# led-er.net
KiCad netlist of a schematic drawn in EAGLE
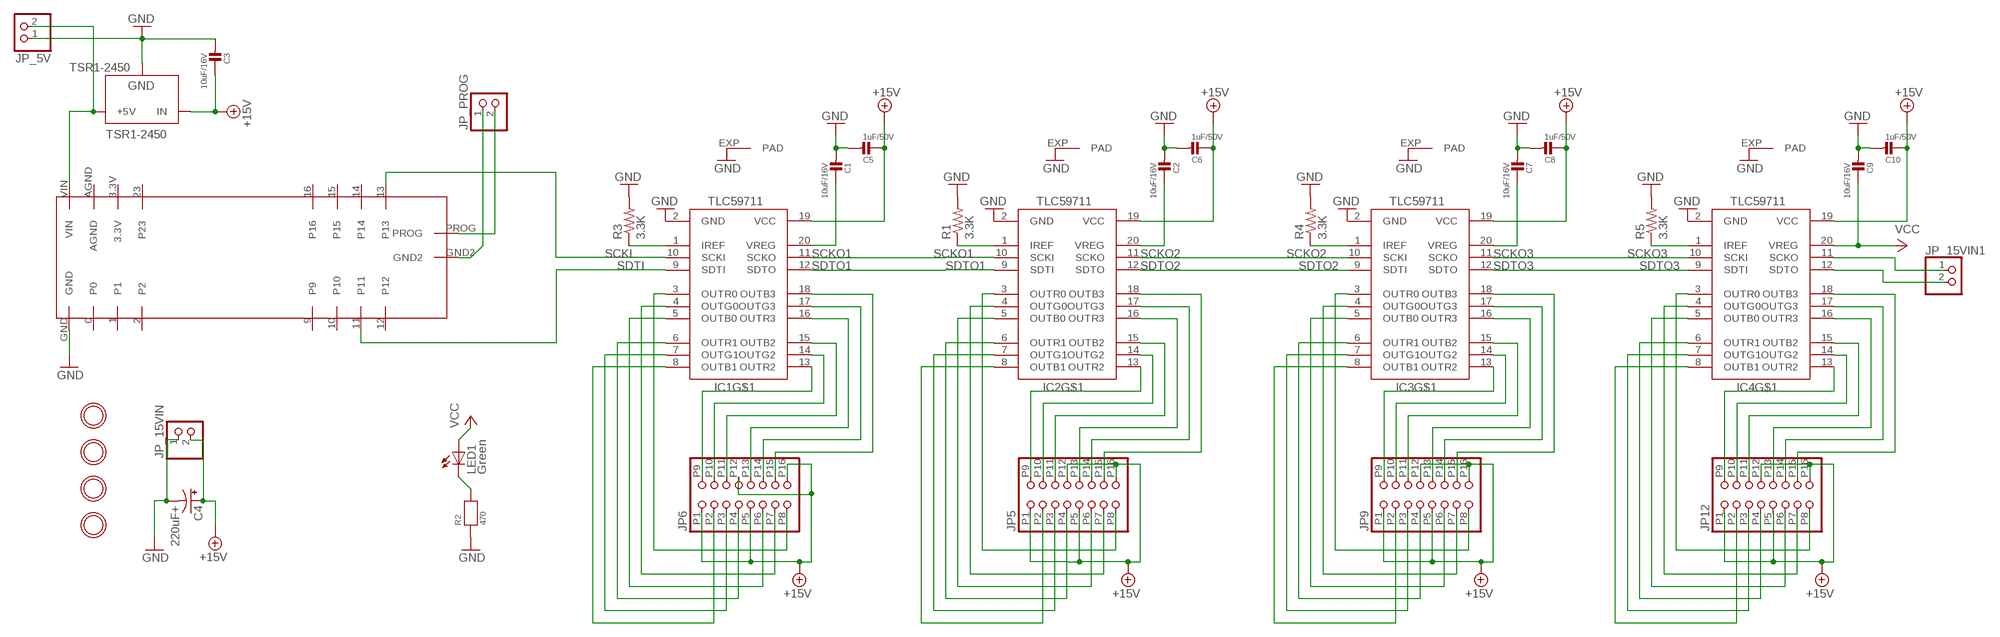
[diagram p0: schematic, sheet 1]

(export (version "E")
  (design (tool "Eeschema 10.0.6"))
  (components
    (comp (ref "C1")
      (value "10uF/16V")
      (footprint "eagle-import:0805")
      (libsource (lib "eagle-import") (part "CAP_CERAMIC0805"))
    )
    (comp (ref "C2")
      (value "10uF/16V")
      (footprint "eagle-import:0805")
      (libsource (lib "eagle-import") (part "CAP_CERAMIC0805"))
    )
    (comp (ref "C3")
      (value "10uF/16V")
      (footprint "eagle-import:0805")
      (libsource (lib "eagle-import") (part "CAP_CERAMIC0805"))
    )
    (comp (ref "C4")
      (value "220uF+")
      (footprint "eagle-import:E5-8,5")
      (libsource (lib "eagle-import") (part "CPOL-USE5-8.5"))
    )
    (comp (ref "C5")
      (value "1uF/50V")
      (footprint "eagle-import:0805")
      (libsource (lib "eagle-import") (part "CAP_CERAMIC0805"))
    )
    (comp (ref "C6")
      (value "1uF/50V")
      (footprint "eagle-import:0805")
      (libsource (lib "eagle-import") (part "CAP_CERAMIC0805"))
    )
    (comp (ref "C7")
      (value "10uF/16V")
      (footprint "eagle-import:0805")
      (libsource (lib "eagle-import") (part "CAP_CERAMIC0805"))
    )
    (comp (ref "C8")
      (value "1uF/50V")
      (footprint "eagle-import:0805")
      (libsource (lib "eagle-import") (part "CAP_CERAMIC0805"))
    )
    (comp (ref "C9")
      (value "10uF/16V")
      (footprint "eagle-import:0805")
      (libsource (lib "eagle-import") (part "CAP_CERAMIC0805"))
    )
    (comp (ref "C10")
      (value "1uF/50V")
      (footprint "eagle-import:0805")
      (libsource (lib "eagle-import") (part "CAP_CERAMIC0805"))
    )
    (comp (ref "IC1")
      (value "TLC59711")
      (footprint "eagle-import:HTSSOP20DAP")
      (libsource (lib "eagle-import") (part "TLC59711"))
    )
    (comp (ref "IC2")
      (value "TLC59711")
      (footprint "eagle-import:HTSSOP20DAP")
      (libsource (lib "eagle-import") (part "TLC59711"))
    )
    (comp (ref "IC3")
      (value "TLC59711")
      (footprint "eagle-import:HTSSOP20DAP")
      (libsource (lib "eagle-import") (part "TLC59711"))
    )
    (comp (ref "IC4")
      (value "TLC59711")
      (footprint "eagle-import:HTSSOP20DAP")
      (libsource (lib "eagle-import") (part "TLC59711"))
    )
    (comp (ref "JP5")
      (value "HEADER-2X8")
      (footprint "eagle-import:2X08")
      (libsource (lib "eagle-import") (part "HEADER-2X8"))
    )
    (comp (ref "JP6")
      (value "HEADER-2X8")
      (footprint "eagle-import:2X08")
      (libsource (lib "eagle-import") (part "HEADER-2X8"))
    )
    (comp (ref "JP9")
      (value "HEADER-2X8")
      (footprint "eagle-import:2X08")
      (libsource (lib "eagle-import") (part "HEADER-2X8"))
    )
    (comp (ref "JP12")
      (value "HEADER-2X8")
      (footprint "eagle-import:2X08")
      (libsource (lib "eagle-import") (part "HEADER-2X8"))
    )
    (comp (ref "JP_5V")
      (value "HEADER-1X2")
      (footprint "eagle-import:1X02_OVAL")
      (libsource (lib "eagle-import") (part "HEADER-1X2"))
    )
    (comp (ref "JP_15VIN")
      (value "HEADER-1X2")
      (footprint "eagle-import:1X02_OVAL")
      (libsource (lib "eagle-import") (part "HEADER-1X2"))
    )
    (comp (ref "JP_15VIN1")
      (value "HEADER-1X2")
      (footprint "eagle-import:1X02_OVAL")
      (libsource (lib "eagle-import") (part "HEADER-1X2"))
    )
    (comp (ref "JP_PROG")
      (value "HEADER-1X2")
      (footprint "eagle-import:1X02_OVAL")
      (libsource (lib "eagle-import") (part "HEADER-1X2"))
    )
    (comp (ref "LED1")
      (value "Green")
      (footprint "eagle-import:CHIP-LED0805")
      (libsource (lib "eagle-import") (part "LEDCHIP-LED0805"))
    )
    (comp (ref "R1")
      (value "3.3K")
      (footprint "eagle-import:0805-THM-7")
      (libsource (lib "eagle-import") (part "R-US_FLIPFLOP7"))
    )
    (comp (ref "R2")
      (value "470")
      (footprint "eagle-import:0805")
      (libsource (lib "eagle-import") (part "RESISTOR0805"))
    )
    (comp (ref "R3")
      (value "3.3K")
      (footprint "eagle-import:0805-THM-7")
      (libsource (lib "eagle-import") (part "R-US_FLIPFLOP7"))
    )
    (comp (ref "R4")
      (value "3.3K")
      (footprint "eagle-import:0805-THM-7")
      (libsource (lib "eagle-import") (part "R-US_FLIPFLOP7"))
    )
    (comp (ref "R5")
      (value "3.3K")
      (footprint "eagle-import:0805-THM-7")
      (libsource (lib "eagle-import") (part "R-US_FLIPFLOP7"))
    )
    (comp (ref "TSR1-2450")
      (value "TSR1-2450")
      (footprint "eagle-import:TSR-1")
      (libsource (lib "eagle-import") (part "TSR1-2450"))
    )
    (comp (ref "U$1")
      (value "MOUNTINGHOLE")
      (footprint "eagle-import:MOUNTINGHOLE_3.0_PLATED")
      (libsource (lib "eagle-import") (part "MOUNTINGHOLE"))
    )
    (comp (ref "U$2")
      (value "MOUNTINGHOLE")
      (footprint "eagle-import:MOUNTINGHOLE_3.0_PLATED")
      (libsource (lib "eagle-import") (part "MOUNTINGHOLE"))
    )
    (comp (ref "U$3")
      (value "MOUNTINGHOLE")
      (footprint "eagle-import:MOUNTINGHOLE_3.0_PLATED")
      (libsource (lib "eagle-import") (part "MOUNTINGHOLE"))
    )
    (comp (ref "U$4")
      (value "MOUNTINGHOLE")
      (footprint "eagle-import:MOUNTINGHOLE_3.0_PLATED")
      (libsource (lib "eagle-import") (part "MOUNTINGHOLE"))
    )
    (comp (ref "U$5")
      (value "TEENSY_LEDER")
      (footprint "eagle-import:TEENSY_LEDER")
      (libsource (lib "eagle-import") (part "TEENSY_LEDER"))
    )
  )
  (nets
    (net (code "1") (name "+15V") (class "Default")
      (node (ref "C10") (pin "1") (pinfunction "P$1_1") (pintype "passive"))
      (node (ref "C3") (pin "1") (pinfunction "P$1_1") (pintype "passive"))
      (node (ref "C4") (pin "+") (pinfunction "+_+") (pintype "passive"))
      (node (ref "C5") (pin "1") (pinfunction "P$1_1") (pintype "passive"))
      (node (ref "C6") (pin "1") (pinfunction "P$1_1") (pintype "passive"))
      (node (ref "C8") (pin "1") (pinfunction "P$1_1") (pintype "passive"))
      (node (ref "IC1") (pin "19") (pinfunction "VCC_19") (pintype "power_in"))
      (node (ref "IC2") (pin "19") (pinfunction "VCC_19") (pintype "power_in"))
      (node (ref "IC3") (pin "19") (pinfunction "VCC_19") (pintype "power_in"))
      (node (ref "IC4") (pin "19") (pinfunction "VCC_19") (pintype "power_in"))
      (node (ref "JP12") (pin "P1") (pinfunction "P1_P1") (pintype "passive"))
      (node (ref "JP12") (pin "P12") (pinfunction "P12_P12") (pintype "passive"))
      (node (ref "JP12") (pin "P16") (pinfunction "P16_P16") (pintype "passive"))
      (node (ref "JP12") (pin "P5") (pinfunction "P5_P5") (pintype "passive"))
      (node (ref "JP5") (pin "P1") (pinfunction "P1_P1") (pintype "passive"))
      (node (ref "JP5") (pin "P12") (pinfunction "P12_P12") (pintype "passive"))
      (node (ref "JP5") (pin "P16") (pinfunction "P16_P16") (pintype "passive"))
      (node (ref "JP5") (pin "P5") (pinfunction "P5_P5") (pintype "passive"))
      (node (ref "JP6") (pin "P1") (pinfunction "P1_P1") (pintype "passive"))
      (node (ref "JP6") (pin "P12") (pinfunction "P12_P12") (pintype "passive"))
      (node (ref "JP6") (pin "P16") (pinfunction "P16_P16") (pintype "passive"))
      (node (ref "JP6") (pin "P5") (pinfunction "P5_P5") (pintype "passive"))
      (node (ref "JP9") (pin "P1") (pinfunction "P1_P1") (pintype "passive"))
      (node (ref "JP9") (pin "P12") (pinfunction "P12_P12") (pintype "passive"))
      (node (ref "JP9") (pin "P16") (pinfunction "P16_P16") (pintype "passive"))
      (node (ref "JP9") (pin "P5") (pinfunction "P5_P5") (pintype "passive"))
      (node (ref "JP_15VIN") (pin "2") (pinfunction "2_2") (pintype "passive"))
      (node (ref "TSR1-2450") (pin "1") (pinfunction "IN_1") (pintype "power_in"))
    )
    (net (code "2") (name "/SCKI") (class "Default")
      (node (ref "IC1") (pin "10") (pinfunction "SCKI_10") (pintype "input"))
      (node (ref "U$5") (pin "13") (pinfunction "P13_13") (pintype "bidirectional"))
    )
    (net (code "3") (name "/SCKO1") (class "Default")
      (node (ref "IC1") (pin "11") (pinfunction "SCKO_11") (pintype "output"))
      (node (ref "IC2") (pin "10") (pinfunction "SCKI_10") (pintype "input"))
    )
    (net (code "4") (name "/SCKO2") (class "Default")
      (node (ref "IC2") (pin "11") (pinfunction "SCKO_11") (pintype "output"))
      (node (ref "IC3") (pin "10") (pinfunction "SCKI_10") (pintype "input"))
    )
    (net (code "5") (name "/SCKO3") (class "Default")
      (node (ref "IC3") (pin "11") (pinfunction "SCKO_11") (pintype "output"))
      (node (ref "IC4") (pin "10") (pinfunction "SCKI_10") (pintype "input"))
    )
    (net (code "6") (name "/SDTI") (class "Default")
      (node (ref "IC1") (pin "9") (pinfunction "SDTI_9") (pintype "input"))
      (node (ref "U$5") (pin "11") (pinfunction "P11_11") (pintype "bidirectional"))
    )
    (net (code "7") (name "/SDTO1") (class "Default")
      (node (ref "IC1") (pin "12") (pinfunction "SDTO_12") (pintype "output"))
      (node (ref "IC2") (pin "9") (pinfunction "SDTI_9") (pintype "input"))
    )
    (net (code "8") (name "/SDTO2") (class "Default")
      (node (ref "IC2") (pin "12") (pinfunction "SDTO_12") (pintype "output"))
      (node (ref "IC3") (pin "9") (pinfunction "SDTI_9") (pintype "input"))
    )
    (net (code "9") (name "/SDTO3") (class "Default")
      (node (ref "IC3") (pin "12") (pinfunction "SDTO_12") (pintype "output"))
      (node (ref "IC4") (pin "9") (pinfunction "SDTI_9") (pintype "input"))
    )
    (net (code "10") (name "GND") (class "Default")
      (node (ref "C1") (pin "2") (pinfunction "P$2_2") (pintype "passive"))
      (node (ref "C10") (pin "2") (pinfunction "P$2_2") (pintype "passive"))
      (node (ref "C2") (pin "2") (pinfunction "P$2_2") (pintype "passive"))
      (node (ref "C3") (pin "2") (pinfunction "P$2_2") (pintype "passive"))
      (node (ref "C4") (pin "-") (pinfunction "-_-") (pintype "passive"))
      (node (ref "C5") (pin "2") (pinfunction "P$2_2") (pintype "passive"))
      (node (ref "C6") (pin "2") (pinfunction "P$2_2") (pintype "passive"))
      (node (ref "C7") (pin "2") (pinfunction "P$2_2") (pintype "passive"))
      (node (ref "C8") (pin "2") (pinfunction "P$2_2") (pintype "passive"))
      (node (ref "C9") (pin "2") (pinfunction "P$2_2") (pintype "passive"))
      (node (ref "IC1") (pin "2") (pinfunction "GND_2") (pintype "power_in"))
      (node (ref "IC1") (pin "EXP") (pinfunction "PAD_EXP") (pintype "passive"))
      (node (ref "IC2") (pin "2") (pinfunction "GND_2") (pintype "power_in"))
      (node (ref "IC2") (pin "EXP") (pinfunction "PAD_EXP") (pintype "passive"))
      (node (ref "IC3") (pin "2") (pinfunction "GND_2") (pintype "power_in"))
      (node (ref "IC3") (pin "EXP") (pinfunction "PAD_EXP") (pintype "passive"))
      (node (ref "IC4") (pin "2") (pinfunction "GND_2") (pintype "power_in"))
      (node (ref "IC4") (pin "EXP") (pinfunction "PAD_EXP") (pintype "passive"))
      (node (ref "JP_15VIN") (pin "1") (pinfunction "1_1") (pintype "passive"))
      (node (ref "JP_5V") (pin "1") (pinfunction "1_1") (pintype "passive"))
      (node (ref "R1") (pin "2") (pinfunction "2_2") (pintype "passive"))
      (node (ref "R2") (pin "1") (pinfunction "1_1") (pintype "passive"))
      (node (ref "R3") (pin "2") (pinfunction "2_2") (pintype "passive"))
      (node (ref "R4") (pin "2") (pinfunction "2_2") (pintype "passive"))
      (node (ref "R5") (pin "2") (pinfunction "2_2") (pintype "passive"))
      (node (ref "TSR1-2450") (pin "2") (pinfunction "GND_2") (pintype "power_in"))
      (node (ref "U$5") (pin "GND") (pinfunction "GND_GND") (pintype "bidirectional"))
    )
    (net (code "11") (name "Net-(C1-P$1)") (class "Default")
      (node (ref "C1") (pin "1") (pinfunction "P$1_1") (pintype "passive"))
      (node (ref "IC1") (pin "20") (pinfunction "VREG_20") (pintype "bidirectional"))
    )
    (net (code "12") (name "Net-(C2-P$1)") (class "Default")
      (node (ref "C2") (pin "1") (pinfunction "P$1_1") (pintype "passive"))
      (node (ref "IC2") (pin "20") (pinfunction "VREG_20") (pintype "bidirectional"))
    )
    (net (code "13") (name "Net-(C7-P$1)") (class "Default")
      (node (ref "C7") (pin "1") (pinfunction "P$1_1") (pintype "passive"))
      (node (ref "IC3") (pin "20") (pinfunction "VREG_20") (pintype "bidirectional"))
    )
    (net (code "14") (name "Net-(IC1A-IREF)") (class "Default")
      (node (ref "IC1") (pin "1") (pinfunction "IREF_1") (pintype "bidirectional"))
      (node (ref "R3") (pin "1") (pinfunction "1_1") (pintype "passive"))
    )
    (net (code "15") (name "Net-(IC1A-OUTB0)") (class "Default")
      (node (ref "IC1") (pin "5") (pinfunction "OUTB0_5") (pintype "open_collector"))
      (node (ref "JP6") (pin "P6") (pinfunction "P6_P6") (pintype "passive"))
    )
    (net (code "16") (name "Net-(IC1A-OUTB1)") (class "Default")
      (node (ref "IC1") (pin "8") (pinfunction "OUTB1_8") (pintype "open_collector"))
      (node (ref "JP6") (pin "P2") (pinfunction "P2_P2") (pintype "passive"))
    )
    (net (code "17") (name "Net-(IC1A-OUTB2)") (class "Default")
      (node (ref "IC1") (pin "15") (pinfunction "OUTB2_15") (pintype "open_collector"))
      (node (ref "JP6") (pin "P11") (pinfunction "P11_P11") (pintype "passive"))
    )
    (net (code "18") (name "Net-(IC1A-OUTB3)") (class "Default")
      (node (ref "IC1") (pin "18") (pinfunction "OUTB3_18") (pintype "open_collector"))
      (node (ref "JP6") (pin "P15") (pinfunction "P15_P15") (pintype "passive"))
    )
    (net (code "19") (name "Net-(IC1A-OUTG0)") (class "Default")
      (node (ref "IC1") (pin "4") (pinfunction "OUTG0_4") (pintype "open_collector"))
      (node (ref "JP6") (pin "P7") (pinfunction "P7_P7") (pintype "passive"))
    )
    (net (code "20") (name "Net-(IC1A-OUTG1)") (class "Default")
      (node (ref "IC1") (pin "7") (pinfunction "OUTG1_7") (pintype "open_collector"))
      (node (ref "JP6") (pin "P3") (pinfunction "P3_P3") (pintype "passive"))
    )
    (net (code "21") (name "Net-(IC1A-OUTG2)") (class "Default")
      (node (ref "IC1") (pin "14") (pinfunction "OUTG2_14") (pintype "open_collector"))
      (node (ref "JP6") (pin "P10") (pinfunction "P10_P10") (pintype "passive"))
    )
    (net (code "22") (name "Net-(IC1A-OUTG3)") (class "Default")
      (node (ref "IC1") (pin "17") (pinfunction "OUTG3_17") (pintype "open_collector"))
      (node (ref "JP6") (pin "P14") (pinfunction "P14_P14") (pintype "passive"))
    )
    (net (code "23") (name "Net-(IC1A-OUTR0)") (class "Default")
      (node (ref "IC1") (pin "3") (pinfunction "OUTR0_3") (pintype "open_collector"))
      (node (ref "JP6") (pin "P8") (pinfunction "P8_P8") (pintype "passive"))
    )
    (net (code "24") (name "Net-(IC1A-OUTR1)") (class "Default")
      (node (ref "IC1") (pin "6") (pinfunction "OUTR1_6") (pintype "open_collector"))
      (node (ref "JP6") (pin "P4") (pinfunction "P4_P4") (pintype "passive"))
    )
    (net (code "25") (name "Net-(IC1A-OUTR2)") (class "Default")
      (node (ref "IC1") (pin "13") (pinfunction "OUTR2_13") (pintype "open_collector"))
      (node (ref "JP6") (pin "P9") (pinfunction "P9_P9") (pintype "passive"))
    )
    (net (code "26") (name "Net-(IC1A-OUTR3)") (class "Default")
      (node (ref "IC1") (pin "16") (pinfunction "OUTR3_16") (pintype "open_collector"))
      (node (ref "JP6") (pin "P13") (pinfunction "P13_P13") (pintype "passive"))
    )
    (net (code "27") (name "Net-(IC2A-IREF)") (class "Default")
      (node (ref "IC2") (pin "1") (pinfunction "IREF_1") (pintype "bidirectional"))
      (node (ref "R1") (pin "1") (pinfunction "1_1") (pintype "passive"))
    )
    (net (code "28") (name "Net-(IC2A-OUTB0)") (class "Default")
      (node (ref "IC2") (pin "5") (pinfunction "OUTB0_5") (pintype "open_collector"))
      (node (ref "JP5") (pin "P6") (pinfunction "P6_P6") (pintype "passive"))
    )
    (net (code "29") (name "Net-(IC2A-OUTB1)") (class "Default")
      (node (ref "IC2") (pin "8") (pinfunction "OUTB1_8") (pintype "open_collector"))
      (node (ref "JP5") (pin "P2") (pinfunction "P2_P2") (pintype "passive"))
    )
    (net (code "30") (name "Net-(IC2A-OUTB2)") (class "Default")
      (node (ref "IC2") (pin "15") (pinfunction "OUTB2_15") (pintype "open_collector"))
      (node (ref "JP5") (pin "P11") (pinfunction "P11_P11") (pintype "passive"))
    )
    (net (code "31") (name "Net-(IC2A-OUTB3)") (class "Default")
      (node (ref "IC2") (pin "18") (pinfunction "OUTB3_18") (pintype "open_collector"))
      (node (ref "JP5") (pin "P15") (pinfunction "P15_P15") (pintype "passive"))
    )
    (net (code "32") (name "Net-(IC2A-OUTG0)") (class "Default")
      (node (ref "IC2") (pin "4") (pinfunction "OUTG0_4") (pintype "open_collector"))
      (node (ref "JP5") (pin "P7") (pinfunction "P7_P7") (pintype "passive"))
    )
    (net (code "33") (name "Net-(IC2A-OUTG1)") (class "Default")
      (node (ref "IC2") (pin "7") (pinfunction "OUTG1_7") (pintype "open_collector"))
      (node (ref "JP5") (pin "P3") (pinfunction "P3_P3") (pintype "passive"))
    )
    (net (code "34") (name "Net-(IC2A-OUTG2)") (class "Default")
      (node (ref "IC2") (pin "14") (pinfunction "OUTG2_14") (pintype "open_collector"))
      (node (ref "JP5") (pin "P10") (pinfunction "P10_P10") (pintype "passive"))
    )
    (net (code "35") (name "Net-(IC2A-OUTG3)") (class "Default")
      (node (ref "IC2") (pin "17") (pinfunction "OUTG3_17") (pintype "open_collector"))
      (node (ref "JP5") (pin "P14") (pinfunction "P14_P14") (pintype "passive"))
    )
    (net (code "36") (name "Net-(IC2A-OUTR0)") (class "Default")
      (node (ref "IC2") (pin "3") (pinfunction "OUTR0_3") (pintype "open_collector"))
      (node (ref "JP5") (pin "P8") (pinfunction "P8_P8") (pintype "passive"))
    )
    (net (code "37") (name "Net-(IC2A-OUTR1)") (class "Default")
      (node (ref "IC2") (pin "6") (pinfunction "OUTR1_6") (pintype "open_collector"))
      (node (ref "JP5") (pin "P4") (pinfunction "P4_P4") (pintype "passive"))
    )
    (net (code "38") (name "Net-(IC2A-OUTR2)") (class "Default")
      (node (ref "IC2") (pin "13") (pinfunction "OUTR2_13") (pintype "open_collector"))
      (node (ref "JP5") (pin "P9") (pinfunction "P9_P9") (pintype "passive"))
    )
    (net (code "39") (name "Net-(IC2A-OUTR3)") (class "Default")
      (node (ref "IC2") (pin "16") (pinfunction "OUTR3_16") (pintype "open_collector"))
      (node (ref "JP5") (pin "P13") (pinfunction "P13_P13") (pintype "passive"))
    )
    (net (code "40") (name "Net-(IC3A-IREF)") (class "Default")
      (node (ref "IC3") (pin "1") (pinfunction "IREF_1") (pintype "bidirectional"))
      (node (ref "R4") (pin "1") (pinfunction "1_1") (pintype "passive"))
    )
    (net (code "41") (name "Net-(IC3A-OUTB0)") (class "Default")
      (node (ref "IC3") (pin "5") (pinfunction "OUTB0_5") (pintype "open_collector"))
      (node (ref "JP9") (pin "P6") (pinfunction "P6_P6") (pintype "passive"))
    )
    (net (code "42") (name "Net-(IC3A-OUTB1)") (class "Default")
      (node (ref "IC3") (pin "8") (pinfunction "OUTB1_8") (pintype "open_collector"))
      (node (ref "JP9") (pin "P2") (pinfunction "P2_P2") (pintype "passive"))
    )
    (net (code "43") (name "Net-(IC3A-OUTB2)") (class "Default")
      (node (ref "IC3") (pin "15") (pinfunction "OUTB2_15") (pintype "open_collector"))
      (node (ref "JP9") (pin "P11") (pinfunction "P11_P11") (pintype "passive"))
    )
    (net (code "44") (name "Net-(IC3A-OUTB3)") (class "Default")
      (node (ref "IC3") (pin "18") (pinfunction "OUTB3_18") (pintype "open_collector"))
      (node (ref "JP9") (pin "P15") (pinfunction "P15_P15") (pintype "passive"))
    )
    (net (code "45") (name "Net-(IC3A-OUTG0)") (class "Default")
      (node (ref "IC3") (pin "4") (pinfunction "OUTG0_4") (pintype "open_collector"))
      (node (ref "JP9") (pin "P7") (pinfunction "P7_P7") (pintype "passive"))
    )
    (net (code "46") (name "Net-(IC3A-OUTG1)") (class "Default")
      (node (ref "IC3") (pin "7") (pinfunction "OUTG1_7") (pintype "open_collector"))
      (node (ref "JP9") (pin "P3") (pinfunction "P3_P3") (pintype "passive"))
    )
    (net (code "47") (name "Net-(IC3A-OUTG2)") (class "Default")
      (node (ref "IC3") (pin "14") (pinfunction "OUTG2_14") (pintype "open_collector"))
      (node (ref "JP9") (pin "P10") (pinfunction "P10_P10") (pintype "passive"))
    )
    (net (code "48") (name "Net-(IC3A-OUTG3)") (class "Default")
      (node (ref "IC3") (pin "17") (pinfunction "OUTG3_17") (pintype "open_collector"))
      (node (ref "JP9") (pin "P14") (pinfunction "P14_P14") (pintype "passive"))
    )
    (net (code "49") (name "Net-(IC3A-OUTR0)") (class "Default")
      (node (ref "IC3") (pin "3") (pinfunction "OUTR0_3") (pintype "open_collector"))
      (node (ref "JP9") (pin "P8") (pinfunction "P8_P8") (pintype "passive"))
    )
    (net (code "50") (name "Net-(IC3A-OUTR1)") (class "Default")
      (node (ref "IC3") (pin "6") (pinfunction "OUTR1_6") (pintype "open_collector"))
      (node (ref "JP9") (pin "P4") (pinfunction "P4_P4") (pintype "passive"))
    )
    (net (code "51") (name "Net-(IC3A-OUTR2)") (class "Default")
      (node (ref "IC3") (pin "13") (pinfunction "OUTR2_13") (pintype "open_collector"))
      (node (ref "JP9") (pin "P9") (pinfunction "P9_P9") (pintype "passive"))
    )
    (net (code "52") (name "Net-(IC3A-OUTR3)") (class "Default")
      (node (ref "IC3") (pin "16") (pinfunction "OUTR3_16") (pintype "open_collector"))
      (node (ref "JP9") (pin "P13") (pinfunction "P13_P13") (pintype "passive"))
    )
    (net (code "53") (name "Net-(IC4A-IREF)") (class "Default")
      (node (ref "IC4") (pin "1") (pinfunction "IREF_1") (pintype "bidirectional"))
      (node (ref "R5") (pin "1") (pinfunction "1_1") (pintype "passive"))
    )
    (net (code "54") (name "Net-(IC4A-OUTB0)") (class "Default")
      (node (ref "IC4") (pin "5") (pinfunction "OUTB0_5") (pintype "open_collector"))
      (node (ref "JP12") (pin "P6") (pinfunction "P6_P6") (pintype "passive"))
    )
    (net (code "55") (name "Net-(IC4A-OUTB1)") (class "Default")
      (node (ref "IC4") (pin "8") (pinfunction "OUTB1_8") (pintype "open_collector"))
      (node (ref "JP12") (pin "P2") (pinfunction "P2_P2") (pintype "passive"))
    )
    (net (code "56") (name "Net-(IC4A-OUTB2)") (class "Default")
      (node (ref "IC4") (pin "15") (pinfunction "OUTB2_15") (pintype "open_collector"))
      (node (ref "JP12") (pin "P11") (pinfunction "P11_P11") (pintype "passive"))
    )
    (net (code "57") (name "Net-(IC4A-OUTB3)") (class "Default")
      (node (ref "IC4") (pin "18") (pinfunction "OUTB3_18") (pintype "open_collector"))
      (node (ref "JP12") (pin "P15") (pinfunction "P15_P15") (pintype "passive"))
    )
    (net (code "58") (name "Net-(IC4A-OUTG0)") (class "Default")
      (node (ref "IC4") (pin "4") (pinfunction "OUTG0_4") (pintype "open_collector"))
      (node (ref "JP12") (pin "P7") (pinfunction "P7_P7") (pintype "passive"))
    )
    (net (code "59") (name "Net-(IC4A-OUTG1)") (class "Default")
      (node (ref "IC4") (pin "7") (pinfunction "OUTG1_7") (pintype "open_collector"))
      (node (ref "JP12") (pin "P3") (pinfunction "P3_P3") (pintype "passive"))
    )
    (net (code "60") (name "Net-(IC4A-OUTG2)") (class "Default")
      (node (ref "IC4") (pin "14") (pinfunction "OUTG2_14") (pintype "open_collector"))
      (node (ref "JP12") (pin "P10") (pinfunction "P10_P10") (pintype "passive"))
    )
    (net (code "61") (name "Net-(IC4A-OUTG3)") (class "Default")
      (node (ref "IC4") (pin "17") (pinfunction "OUTG3_17") (pintype "open_collector"))
      (node (ref "JP12") (pin "P14") (pinfunction "P14_P14") (pintype "passive"))
    )
    (net (code "62") (name "Net-(IC4A-OUTR0)") (class "Default")
      (node (ref "IC4") (pin "3") (pinfunction "OUTR0_3") (pintype "open_collector"))
      (node (ref "JP12") (pin "P8") (pinfunction "P8_P8") (pintype "passive"))
    )
    (net (code "63") (name "Net-(IC4A-OUTR1)") (class "Default")
      (node (ref "IC4") (pin "6") (pinfunction "OUTR1_6") (pintype "open_collector"))
      (node (ref "JP12") (pin "P4") (pinfunction "P4_P4") (pintype "passive"))
    )
    (net (code "64") (name "Net-(IC4A-OUTR2)") (class "Default")
      (node (ref "IC4") (pin "13") (pinfunction "OUTR2_13") (pintype "open_collector"))
      (node (ref "JP12") (pin "P9") (pinfunction "P9_P9") (pintype "passive"))
    )
    (net (code "65") (name "Net-(IC4A-OUTR3)") (class "Default")
      (node (ref "IC4") (pin "16") (pinfunction "OUTR3_16") (pintype "open_collector"))
      (node (ref "JP12") (pin "P13") (pinfunction "P13_P13") (pintype "passive"))
    )
    (net (code "66") (name "Net-(IC4A-SCKO)") (class "Default")
      (node (ref "IC4") (pin "11") (pinfunction "SCKO_11") (pintype "output"))
      (node (ref "JP_15VIN1") (pin "1") (pinfunction "1_1") (pintype "passive"))
    )
    (net (code "67") (name "Net-(IC4A-SDTO)") (class "Default")
      (node (ref "IC4") (pin "12") (pinfunction "SDTO_12") (pintype "output"))
      (node (ref "JP_15VIN1") (pin "2") (pinfunction "2_2") (pintype "passive"))
    )
    (net (code "68") (name "Net-(JP_PROG-Pad1)") (class "Default")
      (node (ref "JP_PROG") (pin "1") (pinfunction "1_1") (pintype "passive"))
      (node (ref "U$5") (pin "GND2") (pinfunction "GND2_GND2") (pintype "bidirectional"))
    )
    (net (code "69") (name "Net-(JP_PROG-Pad2)") (class "Default")
      (node (ref "JP_PROG") (pin "2") (pinfunction "2_2") (pintype "passive"))
      (node (ref "U$5") (pin "PROG") (pinfunction "PROG_PROG") (pintype "bidirectional"))
    )
    (net (code "70") (name "Net-(LED1-PadC)") (class "Default")
      (node (ref "LED1") (pin "C") (pinfunction "C_C") (pintype "passive"))
      (node (ref "R2") (pin "2") (pinfunction "2_2") (pintype "passive"))
    )
    (net (code "71") (name "Net-(TSR1-2450-+5V)") (class "Default")
      (node (ref "JP_5V") (pin "2") (pinfunction "2_2") (pintype "passive"))
      (node (ref "TSR1-2450") (pin "3") (pinfunction "+5V_3") (pintype "power_in"))
      (node (ref "U$5") (pin "VIN") (pinfunction "VIN_VIN") (pintype "bidirectional"))
    )
    (net (code "72") (name "VCC") (class "Default")
      (node (ref "C9") (pin "1") (pinfunction "P$1_1") (pintype "passive"))
      (node (ref "IC4") (pin "20") (pinfunction "VREG_20") (pintype "bidirectional"))
      (node (ref "LED1") (pin "A") (pinfunction "A_A") (pintype "passive"))
    )
    (net (code "73") (name "unconnected-(U$5-P0-Pad0)") (class "Default")
      (node (ref "U$5") (pin "0") (pinfunction "P0_0") (pintype "bidirectional"))
    )
    (net (code "74") (name "unconnected-(U$5-P1-Pad1)") (class "Default")
      (node (ref "U$5") (pin "1") (pinfunction "P1_1") (pintype "bidirectional"))
    )
    (net (code "75") (name "unconnected-(U$5-P2-Pad2)") (class "Default")
      (node (ref "U$5") (pin "2") (pinfunction "P2_2") (pintype "bidirectional"))
    )
    (net (code "76") (name "unconnected-(U$5-P9-Pad9)") (class "Default")
      (node (ref "U$5") (pin "9") (pinfunction "P9_9") (pintype "bidirectional"))
    )
    (net (code "77") (name "unconnected-(U$5-P10-Pad10)") (class "Default")
      (node (ref "U$5") (pin "10") (pinfunction "P10_10") (pintype "bidirectional"))
    )
    (net (code "78") (name "unconnected-(U$5-P12-Pad12)") (class "Default")
      (node (ref "U$5") (pin "12") (pinfunction "P12_12") (pintype "bidirectional"))
    )
    (net (code "79") (name "unconnected-(U$5-P14-Pad14)") (class "Default")
      (node (ref "U$5") (pin "14") (pinfunction "P14_14") (pintype "bidirectional"))
    )
    (net (code "80") (name "unconnected-(U$5-P15-Pad15)") (class "Default")
      (node (ref "U$5") (pin "15") (pinfunction "P15_15") (pintype "bidirectional"))
    )
    (net (code "81") (name "unconnected-(U$5-P16-Pad16)") (class "Default")
      (node (ref "U$5") (pin "16") (pinfunction "P16_16") (pintype "bidirectional"))
    )
    (net (code "82") (name "unconnected-(U$5-P23-Pad23)") (class "Default")
      (node (ref "U$5") (pin "23") (pinfunction "P23_23") (pintype "bidirectional"))
    )
    (net (code "83") (name "unconnected-(U$5-Pad3.3V)") (class "Default")
      (node (ref "U$5") (pin "3.3V") (pinfunction "3.3V_3.3V") (pintype "bidirectional"))
    )
    (net (code "84") (name "unconnected-(U$5-PadAGND)") (class "Default")
      (node (ref "U$5") (pin "AGND") (pinfunction "AGND_AGND") (pintype "bidirectional"))
    )
  )
)
